# 18650-pi.net
KiCad netlist of a schematic drawn in EAGLE
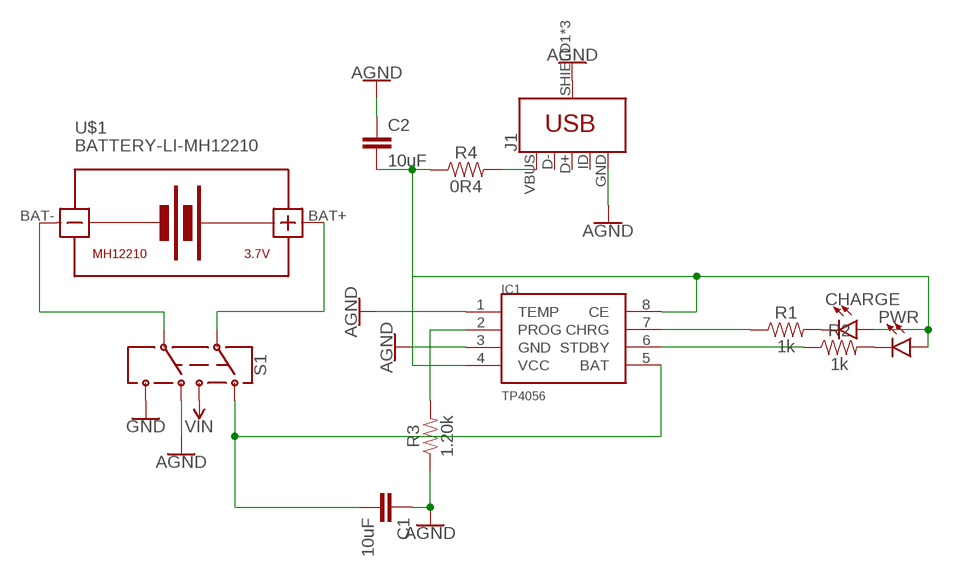
[diagram p0: schematic, sheet 1]
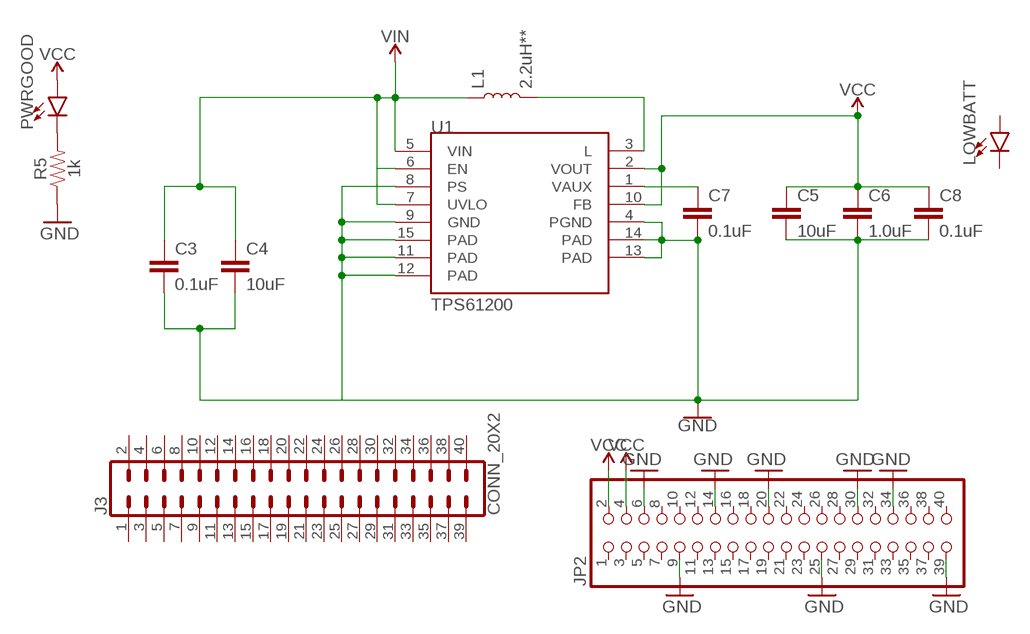
[diagram p1: schematic, sheet 2]

(export (version "E")
  (design (tool "Eeschema 10.0.6"))
  (components
    (comp (ref "C1")
      (value "10uF")
      (footprint "eagle-import:0603")
      (libsource (lib "eagle-import") (part "10UF-0603-6.3V-20%"))
    )
    (comp (ref "C2")
      (value "10uF")
      (footprint "eagle-import:0603")
      (libsource (lib "eagle-import") (part "10UF-0603-6.3V-20%"))
    )
    (comp (ref "CHARGE")
      (value "LED0603")
      (footprint "eagle-import:LED-0603")
      (libsource (lib "eagle-import") (part "LED0603"))
    )
    (comp (ref "IC1")
      (value "TP4056")
      (footprint "eagle-import:SOP-8")
      (libsource (lib "eagle-import") (part "TP4056"))
    )
    (comp (ref "J1")
      (value "USB_MICRO-B_FEMALE-SMT")
      (footprint "eagle-import:USB-B-MICRO-SMD")
      (libsource (lib "eagle-import") (part "USB_MICRO-B_FEMALE-SMT"))
    )
    (comp (ref "PWR")
      (value "LED0603")
      (footprint "eagle-import:LED-0603")
      (libsource (lib "eagle-import") (part "LED0603"))
    )
    (comp (ref "R1")
      (value "1k")
      (footprint "eagle-import:0603")
      (libsource (lib "eagle-import") (part "1KOHM-0603-1/10W-1%"))
    )
    (comp (ref "R2")
      (value "1k")
      (footprint "eagle-import:0603")
      (libsource (lib "eagle-import") (part "1KOHM-0603-1/10W-1%"))
    )
    (comp (ref "R3")
      (value "1.20k")
      (footprint "eagle-import:0603")
      (libsource (lib "eagle-import") (part "1.20KOHM-0603-1/10W-1%"))
    )
    (comp (ref "R4")
      (value "0R4")
      (footprint "eagle-import:0603")
      (libsource (lib "eagle-import") (part "RESISTOR0603"))
    )
    (comp (ref "S1")
      (value "SWITCH-DPDT-SMD-AYZ0202")
      (footprint "eagle-import:SWITCH_DPDT_SMD_AYZ0202")
      (libsource (lib "eagle-import") (part "SWITCH-DPDT-SMD-AYZ0202"))
    )
    (comp (ref "U$1")
      (value "BATTERY-LI-MH12210")
      (footprint "eagle-import:BATTERY-LI-MH12210")
      (libsource (lib "eagle-import") (part "BATTERY-LI-MH12210"))
    )
    (comp (ref "C3")
      (value "0.1uF")
      (footprint "eagle-import:0603")
      (libsource (lib "eagle-import") (part "0.1UF-0603-25V-(+80/-20%)"))
    )
    (comp (ref "C4")
      (value "10uF")
      (footprint "eagle-import:0603")
      (libsource (lib "eagle-import") (part "10UF-0603-6.3V-20%"))
    )
    (comp (ref "C5")
      (value "10uF")
      (footprint "eagle-import:0603")
      (libsource (lib "eagle-import") (part "10UF-0603-6.3V-20%"))
    )
    (comp (ref "C6")
      (value "1.0uF")
      (footprint "eagle-import:0603")
      (libsource (lib "eagle-import") (part "1.0UF-0603-16V-10%"))
    )
    (comp (ref "C7")
      (value "0.1uF")
      (footprint "eagle-import:0603")
      (libsource (lib "eagle-import") (part "0.1UF-0603-25V-(+80/-20%)"))
    )
    (comp (ref "C8")
      (value "0.1uF")
      (footprint "eagle-import:0603")
      (libsource (lib "eagle-import") (part "0.1UF-0603-25V-(+80/-20%)"))
    )
    (comp (ref "J3")
      (value "CONN_20X2")
      (footprint "eagle-import:2X20")
      (libsource (lib "eagle-import") (part "CONN_20X2"))
    )
    (comp (ref "JP2")
      (value "PINHD-2X20_2.54-SMD")
      (footprint "eagle-import:2X20SMD")
      (libsource (lib "eagle-import") (part "PINHD-2X20_2.54-SMD"))
    )
    (comp (ref "L1")
      (value "2.2uH**")
      (footprint "eagle-import:INDUCTOR_4.7UH")
      (libsource (lib "eagle-import") (part "INDUCTOR-CDRH-4.7UH"))
    )
    (comp (ref "LOWBATT")
      (value "LED0603")
      (footprint "eagle-import:LED-0603")
      (libsource (lib "eagle-import") (part "LED0603"))
    )
    (comp (ref "PWRGOOD")
      (value "LED0603")
      (footprint "eagle-import:LED-0603")
      (libsource (lib "eagle-import") (part "LED0603"))
    )
    (comp (ref "R5")
      (value "1k")
      (footprint "eagle-import:0603")
      (libsource (lib "eagle-import") (part "1KOHM-0603-1/10W-1%"))
    )
    (comp (ref "U1")
      (value "TPS61200")
      (footprint "eagle-import:QFN-10_PAD")
      (libsource (lib "eagle-import") (part "TPS61200"))
    )
  )
  (nets
    (net (code "1") (name "AGND") (class "Default")
      (node (ref "C1") (pin "1") (pinfunction "1_1") (pintype "passive"))
      (node (ref "C2") (pin "1") (pinfunction "1_1") (pintype "passive"))
      (node (ref "IC1") (pin "1") (pinfunction "TEMP_1") (pintype "bidirectional"))
      (node (ref "IC1") (pin "3") (pinfunction "GND_3") (pintype "bidirectional"))
      (node (ref "J1") (pin "GND") (pinfunction "GND_GND") (pintype "power_in"))
      (node (ref "J1") (pin "SHIELD1") (pinfunction "SHIELD_SHIELD1") (pintype "bidirectional"))
      (node (ref "J1") (pin "SHIELD2") (pinfunction "SHIELD_SHIELD2") (pintype "bidirectional"))
      (node (ref "J1") (pin "SHIELD3") (pinfunction "SHIELD_SHIELD3") (pintype "bidirectional"))
      (node (ref "R3") (pin "1") (pinfunction "1_1") (pintype "passive"))
      (node (ref "S1") (pin "4") (pinfunction "4_4") (pintype "bidirectional"))
    )
    (net (code "2") (name "GND") (class "Default")
      (node (ref "C3") (pin "2") (pinfunction "2_2") (pintype "passive"))
      (node (ref "C4") (pin "2") (pinfunction "2_2") (pintype "passive"))
      (node (ref "C5") (pin "2") (pinfunction "2_2") (pintype "passive"))
      (node (ref "C6") (pin "2") (pinfunction "2_2") (pintype "passive"))
      (node (ref "C7") (pin "2") (pinfunction "2_2") (pintype "passive"))
      (node (ref "C8") (pin "2") (pinfunction "2_2") (pintype "passive"))
      (node (ref "JP2") (pin "14") (pinfunction "14_14") (pintype "passive"))
      (node (ref "JP2") (pin "20") (pinfunction "20_20") (pintype "passive"))
      (node (ref "JP2") (pin "25") (pinfunction "25_25") (pintype "passive"))
      (node (ref "JP2") (pin "30") (pinfunction "30_30") (pintype "passive"))
      (node (ref "JP2") (pin "34") (pinfunction "34_34") (pintype "passive"))
      (node (ref "JP2") (pin "39") (pinfunction "39_39") (pintype "passive"))
      (node (ref "JP2") (pin "6") (pinfunction "6_6") (pintype "passive"))
      (node (ref "JP2") (pin "9") (pinfunction "9_9") (pintype "passive"))
      (node (ref "R5") (pin "1") (pinfunction "1_1") (pintype "passive"))
      (node (ref "S1") (pin "6") (pinfunction "6_6") (pintype "bidirectional"))
      (node (ref "U1") (pin "11") (pinfunction "PAD_11") (pintype "power_in"))
      (node (ref "U1") (pin "12") (pinfunction "PAD_12") (pintype "power_in"))
      (node (ref "U1") (pin "13") (pinfunction "PAD_13") (pintype "power_in"))
      (node (ref "U1") (pin "14") (pinfunction "PAD_14") (pintype "power_in"))
      (node (ref "U1") (pin "15") (pinfunction "PAD_15") (pintype "power_in"))
      (node (ref "U1") (pin "4") (pinfunction "PGND_4") (pintype "power_in"))
      (node (ref "U1") (pin "8") (pinfunction "PS_8") (pintype "input"))
      (node (ref "U1") (pin "9") (pinfunction "GND_9") (pintype "power_in"))
    )
    (net (code "3") (name "Net-(CHARGE-PadC)") (class "Default")
      (node (ref "CHARGE") (pin "C") (pinfunction "C_C") (pintype "passive"))
      (node (ref "R1") (pin "2") (pinfunction "2_2") (pintype "passive"))
    )
    (net (code "4") (name "Net-(IC1-BAT)") (class "Default")
      (node (ref "C1") (pin "2") (pinfunction "2_2") (pintype "passive"))
      (node (ref "IC1") (pin "5") (pinfunction "BAT_5") (pintype "bidirectional"))
      (node (ref "S1") (pin "1") (pinfunction "1_1") (pintype "bidirectional"))
    )
    (net (code "5") (name "Net-(IC1-CE)") (class "Default")
      (node (ref "C2") (pin "2") (pinfunction "2_2") (pintype "passive"))
      (node (ref "CHARGE") (pin "A") (pinfunction "A_A") (pintype "passive"))
      (node (ref "IC1") (pin "4") (pinfunction "VCC_4") (pintype "bidirectional"))
      (node (ref "IC1") (pin "8") (pinfunction "CE_8") (pintype "bidirectional"))
      (node (ref "PWR") (pin "A") (pinfunction "A_A") (pintype "passive"))
      (node (ref "R4") (pin "1") (pinfunction "1_1") (pintype "passive"))
    )
    (net (code "6") (name "Net-(IC1-CHRG)") (class "Default")
      (node (ref "IC1") (pin "7") (pinfunction "CHRG_7") (pintype "bidirectional"))
      (node (ref "R1") (pin "1") (pinfunction "1_1") (pintype "passive"))
    )
    (net (code "7") (name "Net-(IC1-PROG)") (class "Default")
      (node (ref "IC1") (pin "2") (pinfunction "PROG_2") (pintype "bidirectional"))
      (node (ref "R3") (pin "2") (pinfunction "2_2") (pintype "passive"))
    )
    (net (code "8") (name "Net-(IC1-STDBY)") (class "Default")
      (node (ref "IC1") (pin "6") (pinfunction "STDBY_6") (pintype "bidirectional"))
      (node (ref "R2") (pin "1") (pinfunction "1_1") (pintype "passive"))
    )
    (net (code "9") (name "Net-(J1-PadVBUS)") (class "Default")
      (node (ref "J1") (pin "VBUS") (pinfunction "VBUS_VBUS") (pintype "power_in"))
      (node (ref "R4") (pin "2") (pinfunction "2_2") (pintype "passive"))
    )
    (net (code "10") (name "Net-(L1-2)") (class "Default")
      (node (ref "L1") (pin "P$2") (pinfunction "2_P$2") (pintype "passive"))
      (node (ref "U1") (pin "3") (pinfunction "L_3") (pintype "passive"))
    )
    (net (code "11") (name "Net-(PWR-PadC)") (class "Default")
      (node (ref "PWR") (pin "C") (pinfunction "C_C") (pintype "passive"))
      (node (ref "R2") (pin "2") (pinfunction "2_2") (pintype "passive"))
    )
    (net (code "12") (name "Net-(PWRGOOD-PadC)") (class "Default")
      (node (ref "PWRGOOD") (pin "C") (pinfunction "C_C") (pintype "passive"))
      (node (ref "R5") (pin "2") (pinfunction "2_2") (pintype "passive"))
    )
    (net (code "13") (name "Net-(S1-Pad2)") (class "Default")
      (node (ref "S1") (pin "2") (pinfunction "2_2") (pintype "bidirectional"))
      (node (ref "U$1") (pin "BAT+") (pinfunction "BAT+_BAT+") (pintype "power_in"))
    )
    (net (code "14") (name "Net-(S1-Pad5)") (class "Default")
      (node (ref "S1") (pin "5") (pinfunction "5_5") (pintype "bidirectional"))
      (node (ref "U$1") (pin "BAT-") (pinfunction "BAT-_BAT-") (pintype "power_in"))
    )
    (net (code "15") (name "Net-(U1-VAUX)") (class "Default")
      (node (ref "C7") (pin "1") (pinfunction "1_1") (pintype "passive"))
      (node (ref "U1") (pin "1") (pinfunction "VAUX_1") (pintype "passive"))
    )
    (net (code "16") (name "VCC") (class "Default")
      (node (ref "C5") (pin "1") (pinfunction "1_1") (pintype "passive"))
      (node (ref "C6") (pin "1") (pinfunction "1_1") (pintype "passive"))
      (node (ref "C8") (pin "1") (pinfunction "1_1") (pintype "passive"))
      (node (ref "JP2") (pin "2") (pinfunction "2_2") (pintype "passive"))
      (node (ref "JP2") (pin "4") (pinfunction "4_4") (pintype "passive"))
      (node (ref "PWRGOOD") (pin "A") (pinfunction "A_A") (pintype "passive"))
      (node (ref "U1") (pin "10") (pinfunction "FB_10") (pintype "passive"))
      (node (ref "U1") (pin "2") (pinfunction "VOUT_2") (pintype "passive"))
    )
    (net (code "17") (name "VIN") (class "Default")
      (node (ref "C3") (pin "1") (pinfunction "1_1") (pintype "passive"))
      (node (ref "C4") (pin "1") (pinfunction "1_1") (pintype "passive"))
      (node (ref "L1") (pin "P$1") (pinfunction "1_P$1") (pintype "passive"))
      (node (ref "S1") (pin "3") (pinfunction "3_3") (pintype "bidirectional"))
      (node (ref "U1") (pin "5") (pinfunction "VIN_5") (pintype "power_in"))
      (node (ref "U1") (pin "6") (pinfunction "EN_6") (pintype "input"))
      (node (ref "U1") (pin "7") (pinfunction "UVLO_7") (pintype "passive"))
    )
    (net (code "18") (name "unconnected-(J1-PadD+)") (class "Default")
      (node (ref "J1") (pin "D+") (pinfunction "D+_D+") (pintype "bidirectional"))
    )
    (net (code "19") (name "unconnected-(J1-PadD-)") (class "Default")
      (node (ref "J1") (pin "D-") (pinfunction "D-_D-") (pintype "bidirectional"))
    )
    (net (code "20") (name "unconnected-(J1-PadID)") (class "Default")
      (node (ref "J1") (pin "ID") (pinfunction "ID_ID") (pintype "bidirectional"))
    )
    (net (code "21") (name "unconnected-(J3-Pad1)") (class "Default")
      (node (ref "J3") (pin "1") (pinfunction "1_1") (pintype "passive"))
    )
    (net (code "22") (name "unconnected-(J3-Pad2)") (class "Default")
      (node (ref "J3") (pin "2") (pinfunction "2_2") (pintype "passive"))
    )
    (net (code "23") (name "unconnected-(J3-Pad3)") (class "Default")
      (node (ref "J3") (pin "3") (pinfunction "3_3") (pintype "passive"))
    )
    (net (code "24") (name "unconnected-(J3-Pad4)") (class "Default")
      (node (ref "J3") (pin "4") (pinfunction "4_4") (pintype "passive"))
    )
    (net (code "25") (name "unconnected-(J3-Pad5)") (class "Default")
      (node (ref "J3") (pin "5") (pinfunction "5_5") (pintype "passive"))
    )
    (net (code "26") (name "unconnected-(J3-Pad6)") (class "Default")
      (node (ref "J3") (pin "6") (pinfunction "6_6") (pintype "passive"))
    )
    (net (code "27") (name "unconnected-(J3-Pad7)") (class "Default")
      (node (ref "J3") (pin "7") (pinfunction "7_7") (pintype "passive"))
    )
    (net (code "28") (name "unconnected-(J3-Pad8)") (class "Default")
      (node (ref "J3") (pin "8") (pinfunction "8_8") (pintype "passive"))
    )
    (net (code "29") (name "unconnected-(J3-Pad9)") (class "Default")
      (node (ref "J3") (pin "9") (pinfunction "9_9") (pintype "passive"))
    )
    (net (code "30") (name "unconnected-(J3-Pad10)") (class "Default")
      (node (ref "J3") (pin "10") (pinfunction "10_10") (pintype "passive"))
    )
    (net (code "31") (name "unconnected-(J3-Pad11)") (class "Default")
      (node (ref "J3") (pin "11") (pinfunction "11_11") (pintype "passive"))
    )
    (net (code "32") (name "unconnected-(J3-Pad12)") (class "Default")
      (node (ref "J3") (pin "12") (pinfunction "12_12") (pintype "passive"))
    )
    (net (code "33") (name "unconnected-(J3-Pad13)") (class "Default")
      (node (ref "J3") (pin "13") (pinfunction "13_13") (pintype "passive"))
    )
    (net (code "34") (name "unconnected-(J3-Pad14)") (class "Default")
      (node (ref "J3") (pin "14") (pinfunction "14_14") (pintype "passive"))
    )
    (net (code "35") (name "unconnected-(J3-Pad15)") (class "Default")
      (node (ref "J3") (pin "15") (pinfunction "15_15") (pintype "passive"))
    )
    (net (code "36") (name "unconnected-(J3-Pad16)") (class "Default")
      (node (ref "J3") (pin "16") (pinfunction "16_16") (pintype "passive"))
    )
    (net (code "37") (name "unconnected-(J3-Pad17)") (class "Default")
      (node (ref "J3") (pin "17") (pinfunction "17_17") (pintype "passive"))
    )
    (net (code "38") (name "unconnected-(J3-Pad18)") (class "Default")
      (node (ref "J3") (pin "18") (pinfunction "18_18") (pintype "passive"))
    )
    (net (code "39") (name "unconnected-(J3-Pad19)") (class "Default")
      (node (ref "J3") (pin "19") (pinfunction "19_19") (pintype "passive"))
    )
    (net (code "40") (name "unconnected-(J3-Pad20)") (class "Default")
      (node (ref "J3") (pin "20") (pinfunction "20_20") (pintype "passive"))
    )
    (net (code "41") (name "unconnected-(J3-Pad21)") (class "Default")
      (node (ref "J3") (pin "21") (pinfunction "21_21") (pintype "passive"))
    )
    (net (code "42") (name "unconnected-(J3-Pad22)") (class "Default")
      (node (ref "J3") (pin "22") (pinfunction "22_22") (pintype "passive"))
    )
    (net (code "43") (name "unconnected-(J3-Pad23)") (class "Default")
      (node (ref "J3") (pin "23") (pinfunction "23_23") (pintype "passive"))
    )
    (net (code "44") (name "unconnected-(J3-Pad24)") (class "Default")
      (node (ref "J3") (pin "24") (pinfunction "24_24") (pintype "passive"))
    )
    (net (code "45") (name "unconnected-(J3-Pad25)") (class "Default")
      (node (ref "J3") (pin "25") (pinfunction "25_25") (pintype "passive"))
    )
    (net (code "46") (name "unconnected-(J3-Pad26)") (class "Default")
      (node (ref "J3") (pin "26") (pinfunction "26_26") (pintype "passive"))
    )
    (net (code "47") (name "unconnected-(J3-Pad27)") (class "Default")
      (node (ref "J3") (pin "27") (pinfunction "27_27") (pintype "passive"))
    )
    (net (code "48") (name "unconnected-(J3-Pad28)") (class "Default")
      (node (ref "J3") (pin "28") (pinfunction "28_28") (pintype "passive"))
    )
    (net (code "49") (name "unconnected-(J3-Pad29)") (class "Default")
      (node (ref "J3") (pin "29") (pinfunction "29_29") (pintype "passive"))
    )
    (net (code "50") (name "unconnected-(J3-Pad30)") (class "Default")
      (node (ref "J3") (pin "30") (pinfunction "30_30") (pintype "passive"))
    )
    (net (code "51") (name "unconnected-(J3-Pad31)") (class "Default")
      (node (ref "J3") (pin "31") (pinfunction "31_31") (pintype "passive"))
    )
    (net (code "52") (name "unconnected-(J3-Pad32)") (class "Default")
      (node (ref "J3") (pin "32") (pinfunction "32_32") (pintype "passive"))
    )
    (net (code "53") (name "unconnected-(J3-Pad33)") (class "Default")
      (node (ref "J3") (pin "33") (pinfunction "33_33") (pintype "passive"))
    )
    (net (code "54") (name "unconnected-(J3-Pad34)") (class "Default")
      (node (ref "J3") (pin "34") (pinfunction "34_34") (pintype "passive"))
    )
    (net (code "55") (name "unconnected-(J3-Pad35)") (class "Default")
      (node (ref "J3") (pin "35") (pinfunction "35_35") (pintype "passive"))
    )
    (net (code "56") (name "unconnected-(J3-Pad36)") (class "Default")
      (node (ref "J3") (pin "36") (pinfunction "36_36") (pintype "passive"))
    )
    (net (code "57") (name "unconnected-(J3-Pad37)") (class "Default")
      (node (ref "J3") (pin "37") (pinfunction "37_37") (pintype "passive"))
    )
    (net (code "58") (name "unconnected-(J3-Pad38)") (class "Default")
      (node (ref "J3") (pin "38") (pinfunction "38_38") (pintype "passive"))
    )
    (net (code "59") (name "unconnected-(J3-Pad39)") (class "Default")
      (node (ref "J3") (pin "39") (pinfunction "39_39") (pintype "passive"))
    )
    (net (code "60") (name "unconnected-(J3-Pad40)") (class "Default")
      (node (ref "J3") (pin "40") (pinfunction "40_40") (pintype "passive"))
    )
    (net (code "61") (name "unconnected-(JP2-Pad1)") (class "Default")
      (node (ref "JP2") (pin "1") (pinfunction "1_1") (pintype "passive"))
    )
    (net (code "62") (name "unconnected-(JP2-Pad3)") (class "Default")
      (node (ref "JP2") (pin "3") (pinfunction "3_3") (pintype "passive"))
    )
    (net (code "63") (name "unconnected-(JP2-Pad5)") (class "Default")
      (node (ref "JP2") (pin "5") (pinfunction "5_5") (pintype "passive"))
    )
    (net (code "64") (name "unconnected-(JP2-Pad7)") (class "Default")
      (node (ref "JP2") (pin "7") (pinfunction "7_7") (pintype "passive"))
    )
    (net (code "65") (name "unconnected-(JP2-Pad8)") (class "Default")
      (node (ref "JP2") (pin "8") (pinfunction "8_8") (pintype "passive"))
    )
    (net (code "66") (name "unconnected-(JP2-Pad10)") (class "Default")
      (node (ref "JP2") (pin "10") (pinfunction "10_10") (pintype "passive"))
    )
    (net (code "67") (name "unconnected-(JP2-Pad11)") (class "Default")
      (node (ref "JP2") (pin "11") (pinfunction "11_11") (pintype "passive"))
    )
    (net (code "68") (name "unconnected-(JP2-Pad12)") (class "Default")
      (node (ref "JP2") (pin "12") (pinfunction "12_12") (pintype "passive"))
    )
    (net (code "69") (name "unconnected-(JP2-Pad13)") (class "Default")
      (node (ref "JP2") (pin "13") (pinfunction "13_13") (pintype "passive"))
    )
    (net (code "70") (name "unconnected-(JP2-Pad15)") (class "Default")
      (node (ref "JP2") (pin "15") (pinfunction "15_15") (pintype "passive"))
    )
    (net (code "71") (name "unconnected-(JP2-Pad16)") (class "Default")
      (node (ref "JP2") (pin "16") (pinfunction "16_16") (pintype "passive"))
    )
    (net (code "72") (name "unconnected-(JP2-Pad17)") (class "Default")
      (node (ref "JP2") (pin "17") (pinfunction "17_17") (pintype "passive"))
    )
    (net (code "73") (name "unconnected-(JP2-Pad18)") (class "Default")
      (node (ref "JP2") (pin "18") (pinfunction "18_18") (pintype "passive"))
    )
    (net (code "74") (name "unconnected-(JP2-Pad19)") (class "Default")
      (node (ref "JP2") (pin "19") (pinfunction "19_19") (pintype "passive"))
    )
    (net (code "75") (name "unconnected-(JP2-Pad21)") (class "Default")
      (node (ref "JP2") (pin "21") (pinfunction "21_21") (pintype "passive"))
    )
    (net (code "76") (name "unconnected-(JP2-Pad22)") (class "Default")
      (node (ref "JP2") (pin "22") (pinfunction "22_22") (pintype "passive"))
    )
    (net (code "77") (name "unconnected-(JP2-Pad23)") (class "Default")
      (node (ref "JP2") (pin "23") (pinfunction "23_23") (pintype "passive"))
    )
    (net (code "78") (name "unconnected-(JP2-Pad24)") (class "Default")
      (node (ref "JP2") (pin "24") (pinfunction "24_24") (pintype "passive"))
    )
    (net (code "79") (name "unconnected-(JP2-Pad26)") (class "Default")
      (node (ref "JP2") (pin "26") (pinfunction "26_26") (pintype "passive"))
    )
    (net (code "80") (name "unconnected-(JP2-Pad27)") (class "Default")
      (node (ref "JP2") (pin "27") (pinfunction "27_27") (pintype "passive"))
    )
    (net (code "81") (name "unconnected-(JP2-Pad28)") (class "Default")
      (node (ref "JP2") (pin "28") (pinfunction "28_28") (pintype "passive"))
    )
    (net (code "82") (name "unconnected-(JP2-Pad29)") (class "Default")
      (node (ref "JP2") (pin "29") (pinfunction "29_29") (pintype "passive"))
    )
    (net (code "83") (name "unconnected-(JP2-Pad31)") (class "Default")
      (node (ref "JP2") (pin "31") (pinfunction "31_31") (pintype "passive"))
    )
    (net (code "84") (name "unconnected-(JP2-Pad32)") (class "Default")
      (node (ref "JP2") (pin "32") (pinfunction "32_32") (pintype "passive"))
    )
    (net (code "85") (name "unconnected-(JP2-Pad33)") (class "Default")
      (node (ref "JP2") (pin "33") (pinfunction "33_33") (pintype "passive"))
    )
    (net (code "86") (name "unconnected-(JP2-Pad35)") (class "Default")
      (node (ref "JP2") (pin "35") (pinfunction "35_35") (pintype "passive"))
    )
    (net (code "87") (name "unconnected-(JP2-Pad36)") (class "Default")
      (node (ref "JP2") (pin "36") (pinfunction "36_36") (pintype "passive"))
    )
    (net (code "88") (name "unconnected-(JP2-Pad37)") (class "Default")
      (node (ref "JP2") (pin "37") (pinfunction "37_37") (pintype "passive"))
    )
    (net (code "89") (name "unconnected-(JP2-Pad38)") (class "Default")
      (node (ref "JP2") (pin "38") (pinfunction "38_38") (pintype "passive"))
    )
    (net (code "90") (name "unconnected-(JP2-Pad40)") (class "Default")
      (node (ref "JP2") (pin "40") (pinfunction "40_40") (pintype "passive"))
    )
    (net (code "91") (name "unconnected-(LOWBATT-PadA)") (class "Default")
      (node (ref "LOWBATT") (pin "A") (pinfunction "A_A") (pintype "passive"))
    )
    (net (code "92") (name "unconnected-(LOWBATT-PadC)") (class "Default")
      (node (ref "LOWBATT") (pin "C") (pinfunction "C_C") (pintype "passive"))
    )
  )
)
